# KEYPAD.net
KiCad netlist of a schematic drawn in Altium Designer
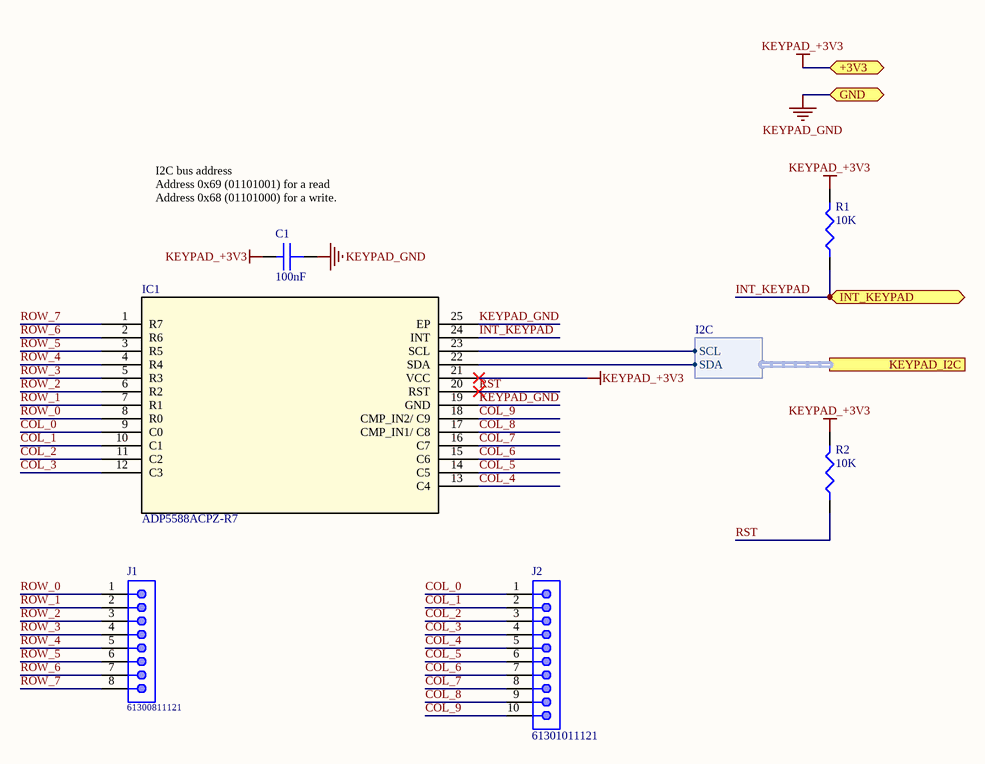
[diagram p0: KEYPAD.SchDoc]

(export (version "E")
  (design (tool "Eeschema 10.0.6"))
  (components
    (comp (ref "C1")
      (value "100nF")
      (footprint "C0603")
      (description "100nF, 25V, X7R, 10%, 0603")
      (fields
        (field (name "MANUFACTURER") "Yageo")
        (field (name "MANUFACTURER PART NUMBER") "CC0603KRX7R8BB104")
      )
      (libsource (lib "McmLibrary") (part "CC0603KRX7R8BB104"))
    )
    (comp (ref "IC1")
      (value "ADP5588ACPZ-R7")
      (footprint "CP_24_1")
      (description "IC KEYPAD SCANNER GPIO PORT EXP")
      (fields (field (name "MANUFACTURER") "Analog Devices"))
      (libsource (lib "McmLibrary") (part "ADP5588ACPZ-R7"))
    )
    (comp (ref "J1")
      (value "61300811121")
      (footprint "61300811121")
      (description "WR-PHD Pin Header, THT, pitch 2.54mm, Single Row, Vertical, 8pin")
      (fields (field (name "MANUFACTURER") "Wurth Electronics") (field (name "PUBLISHER") "Wurth Elektronik"))
      (libsource (lib "McmLibrary") (part "61300811121"))
    )
    (comp (ref "J2")
      (value "61301011121")
      (footprint "61301011121")
      (fields (field (name "MANUFACTURER") "Wurth Electronics"))
      (libsource (lib "McmLibrary") (part "61301011121"))
    )
    (comp (ref "R1")
      (value "10K")
      (footprint "R0603")
      (description "10K OHM 1% 1/10W 0603")
      (fields
        (field (name "MANUFACTURER") "Yageo")
        (field (name "MANUFACTURER PART NUMBER") "RT0603FRE0710KL")
      )
      (libsource (lib "McmLibrary") (part "RT0603FRE0710KL"))
    )
    (comp (ref "R2")
      (value "10K")
      (footprint "R0603")
      (description "10K OHM 1% 1/10W 0603")
      (fields
        (field (name "MANUFACTURER") "Yageo")
        (field (name "MANUFACTURER PART NUMBER") "RT0603FRE0710KL")
      )
      (libsource (lib "McmLibrary") (part "RT0603FRE0710KL"))
    )
  )
  (nets
    (net (code "2") (name "/COL_0") (class "Default")
      (node (ref "IC1") (pin "9") (pinfunction "C0_9") (pintype "passive"))
      (node (ref "J2") (pin "1") (pinfunction "1_1") (pintype "passive"))
    )
    (net (code "3") (name "/COL_1") (class "Default")
      (node (ref "IC1") (pin "10") (pinfunction "C1_10") (pintype "passive"))
      (node (ref "J2") (pin "2") (pinfunction "2_2") (pintype "passive"))
    )
    (net (code "4") (name "/COL_2") (class "Default")
      (node (ref "IC1") (pin "11") (pinfunction "C2_11") (pintype "passive"))
      (node (ref "J2") (pin "3") (pinfunction "3_3") (pintype "passive"))
    )
    (net (code "5") (name "/COL_3") (class "Default")
      (node (ref "IC1") (pin "12") (pinfunction "C3_12") (pintype "passive"))
      (node (ref "J2") (pin "4") (pinfunction "4_4") (pintype "passive"))
    )
    (net (code "6") (name "/COL_4") (class "Default")
      (node (ref "IC1") (pin "13") (pinfunction "C4_13") (pintype "passive"))
      (node (ref "J2") (pin "5") (pinfunction "5_5") (pintype "passive"))
    )
    (net (code "7") (name "/COL_5") (class "Default")
      (node (ref "IC1") (pin "14") (pinfunction "C5_14") (pintype "passive"))
      (node (ref "J2") (pin "6") (pinfunction "6_6") (pintype "passive"))
    )
    (net (code "8") (name "/COL_6") (class "Default")
      (node (ref "IC1") (pin "15") (pinfunction "C6_15") (pintype "passive"))
      (node (ref "J2") (pin "7") (pinfunction "7_7") (pintype "passive"))
    )
    (net (code "9") (name "/COL_7") (class "Default")
      (node (ref "IC1") (pin "16") (pinfunction "C7_16") (pintype "passive"))
      (node (ref "J2") (pin "8") (pinfunction "8_8") (pintype "passive"))
    )
    (net (code "10") (name "/COL_8") (class "Default")
      (node (ref "IC1") (pin "17") (pinfunction "CMP_IN1/_C8_17") (pintype "passive"))
      (node (ref "J2") (pin "9") (pinfunction "9_9") (pintype "passive"))
    )
    (net (code "11") (name "/COL_9") (class "Default")
      (node (ref "IC1") (pin "18") (pinfunction "CMP_IN2/_C9_18") (pintype "passive"))
      (node (ref "J2") (pin "10") (pinfunction "10_10") (pintype "passive"))
    )
    (net (code "12") (name "/INT_KEYPAD") (class "Default")
      (node (ref "IC1") (pin "24") (pinfunction "INT_24") (pintype "passive"))
      (node (ref "R1") (pin "1") (pinfunction "1_1") (pintype "passive"))
    )
    (net (code "13") (name "/ROW_0") (class "Default")
      (node (ref "IC1") (pin "8") (pinfunction "R0_8") (pintype "passive"))
      (node (ref "J1") (pin "1") (pinfunction "1_1") (pintype "passive"))
    )
    (net (code "14") (name "/ROW_1") (class "Default")
      (node (ref "IC1") (pin "7") (pinfunction "R1_7") (pintype "passive"))
      (node (ref "J1") (pin "2") (pinfunction "2_2") (pintype "passive"))
    )
    (net (code "15") (name "/ROW_2") (class "Default")
      (node (ref "IC1") (pin "6") (pinfunction "R2_6") (pintype "passive"))
      (node (ref "J1") (pin "3") (pinfunction "3_3") (pintype "passive"))
    )
    (net (code "16") (name "/ROW_3") (class "Default")
      (node (ref "IC1") (pin "5") (pinfunction "R3_5") (pintype "passive"))
      (node (ref "J1") (pin "4") (pinfunction "4_4") (pintype "passive"))
    )
    (net (code "17") (name "/ROW_4") (class "Default")
      (node (ref "IC1") (pin "4") (pinfunction "R4_4") (pintype "passive"))
      (node (ref "J1") (pin "5") (pinfunction "5_5") (pintype "passive"))
    )
    (net (code "18") (name "/ROW_5") (class "Default")
      (node (ref "IC1") (pin "3") (pinfunction "R5_3") (pintype "passive"))
      (node (ref "J1") (pin "6") (pinfunction "6_6") (pintype "passive"))
    )
    (net (code "19") (name "/ROW_6") (class "Default")
      (node (ref "IC1") (pin "2") (pinfunction "R6_2") (pintype "passive"))
      (node (ref "J1") (pin "7") (pinfunction "7_7") (pintype "passive"))
    )
    (net (code "20") (name "/ROW_7") (class "Default")
      (node (ref "IC1") (pin "1") (pinfunction "R7_1") (pintype "passive"))
      (node (ref "J1") (pin "8") (pinfunction "8_8") (pintype "passive"))
    )
    (net (code "21") (name "/RST") (class "Default")
      (node (ref "IC1") (pin "20") (pinfunction "RST_20") (pintype "passive"))
      (node (ref "R2") (pin "1") (pinfunction "1_1") (pintype "passive"))
    )
    (net (code "22") (name "/SCL") (class "Default")
      (node (ref "IC1") (pin "23") (pinfunction "SCL_23") (pintype "passive"))
    )
    (net (code "23") (name "/SDA") (class "Default")
      (node (ref "IC1") (pin "22") (pinfunction "SDA_22") (pintype "passive"))
    )
    (net (code "25") (name "KEYPAD_+3V3") (class "Default")
      (node (ref "C1") (pin "1") (pintype "passive"))
      (node (ref "IC1") (pin "21") (pinfunction "VCC_21") (pintype "power_in"))
      (node (ref "R1") (pin "2") (pinfunction "2_2") (pintype "passive"))
      (node (ref "R2") (pin "2") (pinfunction "2_2") (pintype "passive"))
    )
    (net (code "26") (name "KEYPAD_GND") (class "Default")
      (node (ref "C1") (pin "2") (pintype "passive"))
      (node (ref "IC1") (pin "19") (pinfunction "GND_19") (pintype "passive"))
      (node (ref "IC1") (pin "25") (pinfunction "EP_25") (pintype "passive"))
    )
  )
)
